# chestnut-tube-amp.net
KiCad netlist of a schematic drawn in EAGLE
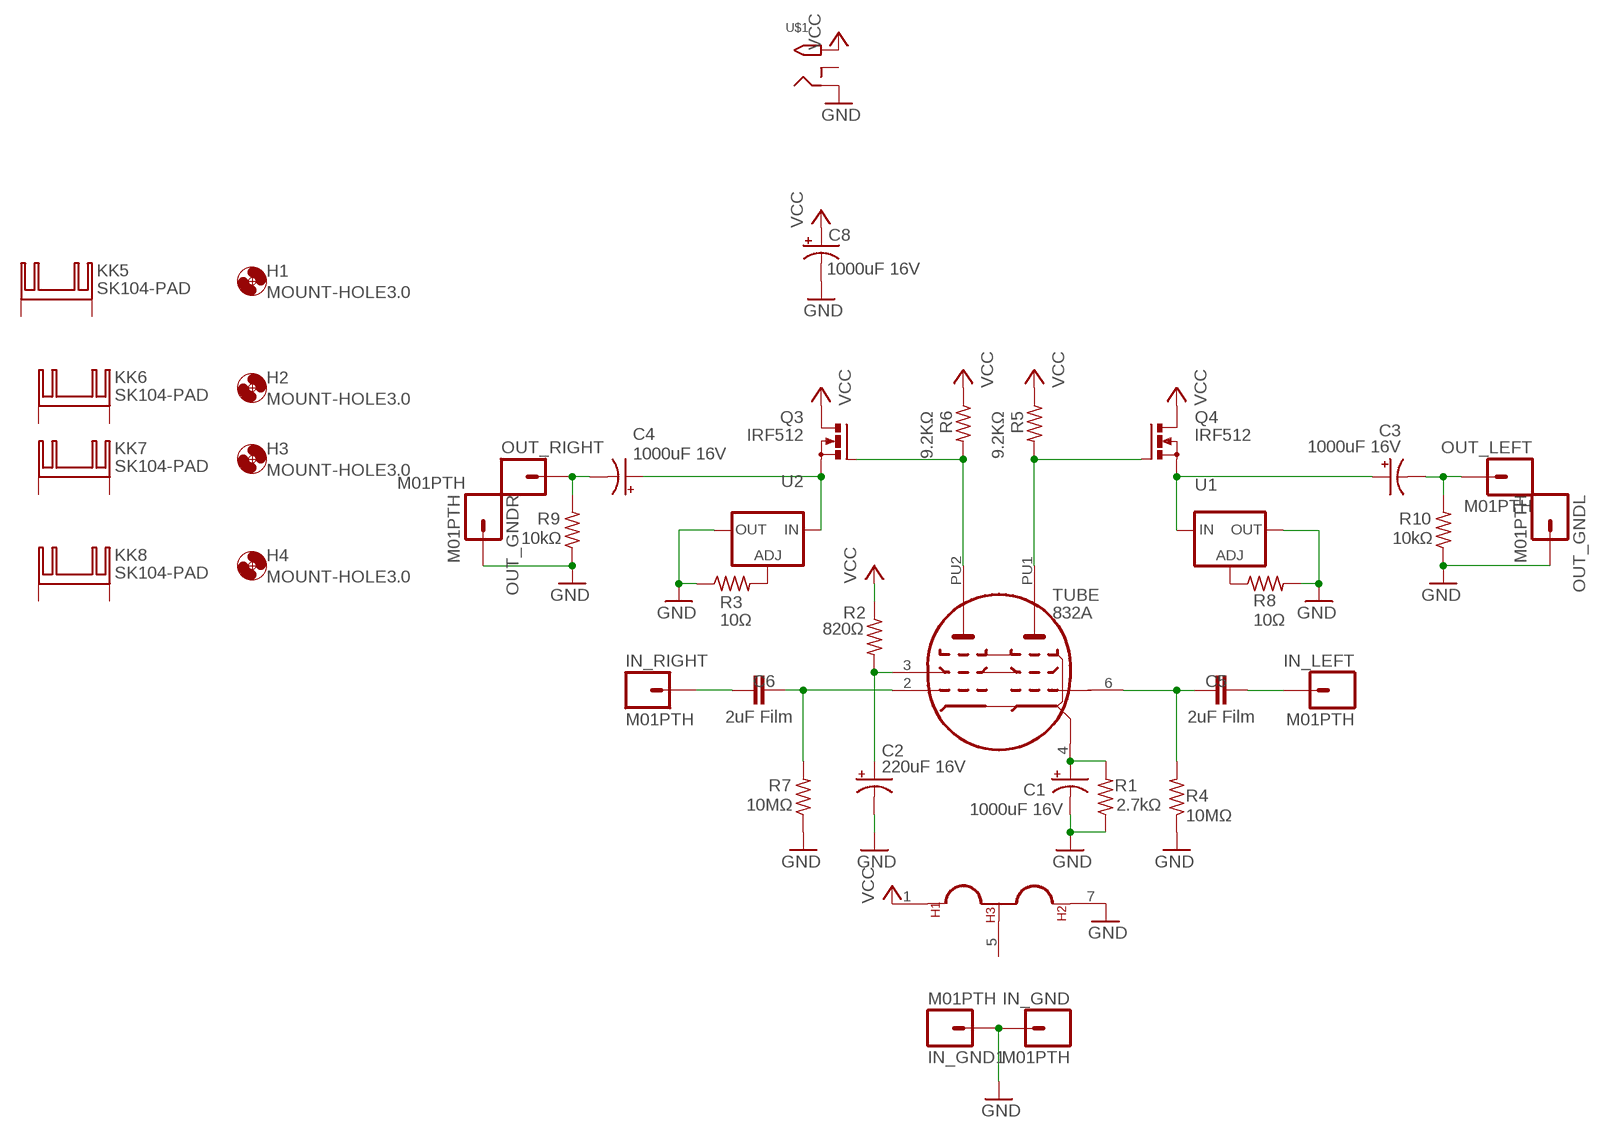
[diagram p0: schematic, sheet 1]

(export (version "E")
  (design (tool "Eeschema 10.0.6"))
  (components
    (comp (ref "C1")
      (value "1000uF 16V")
      (footprint "eagle-import:E5-10,5")
      (libsource (lib "eagle-import") (part "CPOL-USE5-10.5"))
    )
    (comp (ref "C2")
      (value "220uF 16V")
      (footprint "eagle-import:E2,5-7")
      (libsource (lib "eagle-import") (part "CPOL-USE2.5-7"))
    )
    (comp (ref "C3")
      (value "1000uF 16V")
      (footprint "eagle-import:E5-10,5")
      (libsource (lib "eagle-import") (part "CPOL-USE5-10.5"))
    )
    (comp (ref "C4")
      (value "1000uF 16V")
      (footprint "eagle-import:E5-10,5")
      (libsource (lib "eagle-import") (part "CPOL-USE5-10.5"))
    )
    (comp (ref "C5")
      (value "2uF Film")
      (footprint "eagle-import:C375-155X418")
      (libsource (lib "eagle-import") (part "C-EU375-155X418"))
    )
    (comp (ref "C6")
      (value "2uF Film")
      (footprint "eagle-import:C375-155X418")
      (libsource (lib "eagle-import") (part "C-EU375-155X418"))
    )
    (comp (ref "C8")
      (value "1000uF 16V")
      (footprint "eagle-import:E5-10,5")
      (libsource (lib "eagle-import") (part "CPOL-USE5-10.5"))
    )
    (comp (ref "H1")
      (value "MOUNT-HOLE3.0")
      (footprint "eagle-import:3,0")
      (libsource (lib "eagle-import") (part "MOUNT-HOLE3.0"))
    )
    (comp (ref "H2")
      (value "MOUNT-HOLE3.0")
      (footprint "eagle-import:3,0")
      (libsource (lib "eagle-import") (part "MOUNT-HOLE3.0"))
    )
    (comp (ref "H3")
      (value "MOUNT-HOLE3.0")
      (footprint "eagle-import:3,0")
      (libsource (lib "eagle-import") (part "MOUNT-HOLE3.0"))
    )
    (comp (ref "H4")
      (value "MOUNT-HOLE3.0")
      (footprint "eagle-import:3,0")
      (libsource (lib "eagle-import") (part "MOUNT-HOLE3.0"))
    )
    (comp (ref "IN_GND")
      (value "M01PTH")
      (footprint "eagle-import:1X01")
      (libsource (lib "eagle-import") (part "M01PTH"))
    )
    (comp (ref "IN_GND1")
      (value "M01PTH")
      (footprint "eagle-import:1X01")
      (libsource (lib "eagle-import") (part "M01PTH"))
    )
    (comp (ref "IN_LEFT")
      (value "M01PTH")
      (footprint "eagle-import:1X01")
      (libsource (lib "eagle-import") (part "M01PTH"))
    )
    (comp (ref "IN_RIGHT")
      (value "M01PTH")
      (footprint "eagle-import:1X01")
      (libsource (lib "eagle-import") (part "M01PTH"))
    )
    (comp (ref "KK5")
      (value "SK104-PAD")
      (footprint "eagle-import:SK104-PAD")
      (libsource (lib "eagle-import") (part "SK104-PAD"))
    )
    (comp (ref "KK6")
      (value "SK104-PAD")
      (footprint "eagle-import:SK104-PAD")
      (libsource (lib "eagle-import") (part "SK104-PAD"))
    )
    (comp (ref "KK7")
      (value "SK104-PAD")
      (footprint "eagle-import:SK104-PAD")
      (libsource (lib "eagle-import") (part "SK104-PAD"))
    )
    (comp (ref "KK8")
      (value "SK104-PAD")
      (footprint "eagle-import:SK104-PAD")
      (libsource (lib "eagle-import") (part "SK104-PAD"))
    )
    (comp (ref "OUT_GNDL")
      (value "M01PTH")
      (footprint "eagle-import:1X01")
      (libsource (lib "eagle-import") (part "M01PTH"))
    )
    (comp (ref "OUT_GNDR")
      (value "M01PTH")
      (footprint "eagle-import:1X01")
      (libsource (lib "eagle-import") (part "M01PTH"))
    )
    (comp (ref "OUT_LEFT")
      (value "M01PTH")
      (footprint "eagle-import:1X01")
      (libsource (lib "eagle-import") (part "M01PTH"))
    )
    (comp (ref "OUT_RIGHT")
      (value "M01PTH")
      (footprint "eagle-import:1X01")
      (libsource (lib "eagle-import") (part "M01PTH"))
    )
    (comp (ref "Q3")
      (value "IRF512")
      (footprint "eagle-import:TO220BV")
      (libsource (lib "eagle-import") (part "IRF512"))
    )
    (comp (ref "Q4")
      (value "IRF512")
      (footprint "eagle-import:TO220BV")
      (libsource (lib "eagle-import") (part "IRF512"))
    )
    (comp (ref "R1")
      (value "2.7kΩ")
      (footprint "eagle-import:0207_7")
      (libsource (lib "eagle-import") (part "R-US_0207/7"))
    )
    (comp (ref "R2")
      (value "820Ω")
      (footprint "eagle-import:0207_7")
      (libsource (lib "eagle-import") (part "R-US_0207/7"))
    )
    (comp (ref "R3")
      (value "10Ω")
      (footprint "eagle-import:0207_7")
      (libsource (lib "eagle-import") (part "R-US_0207/7"))
    )
    (comp (ref "R4")
      (value "10MΩ")
      (footprint "eagle-import:0207_7")
      (libsource (lib "eagle-import") (part "R-US_0207/7"))
    )
    (comp (ref "R5")
      (value "9.2KΩ")
      (footprint "eagle-import:0207_7")
      (libsource (lib "eagle-import") (part "R-US_0207/7"))
    )
    (comp (ref "R6")
      (value "9.2KΩ")
      (footprint "eagle-import:0207_7")
      (libsource (lib "eagle-import") (part "R-US_0207/7"))
    )
    (comp (ref "R7")
      (value "10MΩ")
      (footprint "eagle-import:0207_7")
      (libsource (lib "eagle-import") (part "R-US_0207/7"))
    )
    (comp (ref "R8")
      (value "10Ω")
      (footprint "eagle-import:0207_7")
      (libsource (lib "eagle-import") (part "R-US_0207/7"))
    )
    (comp (ref "R9")
      (value "10kΩ")
      (footprint "eagle-import:0207_7")
      (libsource (lib "eagle-import") (part "R-US_0207/7"))
    )
    (comp (ref "R10")
      (value "10kΩ")
      (footprint "eagle-import:0207_7")
      (libsource (lib "eagle-import") (part "R-US_0207/7"))
    )
    (comp (ref "TUBE")
      (value "832A")
      (footprint "eagle-import:832A")
      (libsource (lib "eagle-import") (part "832A"))
    )
    (comp (ref "U$1")
      (value "2.1MMJACKTHM")
      (footprint "eagle-import:PJ-102A")
      (libsource (lib "eagle-import") (part "2.1MMJACKTHM"))
    )
    (comp (ref "U1")
      (value "LM317TS")
      (footprint "eagle-import:317TS")
      (libsource (lib "eagle-import") (part "LM317TS"))
    )
    (comp (ref "U2")
      (value "LM317TS")
      (footprint "eagle-import:317TS")
      (libsource (lib "eagle-import") (part "LM317TS"))
    )
  )
  (nets
    (net (code "1") (name "GND") (class "Default")
      (node (ref "C1") (pin "-") (pinfunction "-_-") (pintype "passive"))
      (node (ref "C2") (pin "-") (pinfunction "-_-") (pintype "passive"))
      (node (ref "C8") (pin "-") (pinfunction "-_-") (pintype "passive"))
      (node (ref "IN_GND") (pin "1") (pinfunction "1_1") (pintype "passive"))
      (node (ref "IN_GND1") (pin "1") (pinfunction "1_1") (pintype "passive"))
      (node (ref "OUT_GNDL") (pin "1") (pinfunction "1_1") (pintype "passive"))
      (node (ref "OUT_GNDR") (pin "1") (pinfunction "1_1") (pintype "passive"))
      (node (ref "R1") (pin "1") (pinfunction "1_1") (pintype "passive"))
      (node (ref "R10") (pin "1") (pinfunction "1_1") (pintype "passive"))
      (node (ref "R3") (pin "1") (pinfunction "1_1") (pintype "passive"))
      (node (ref "R4") (pin "1") (pinfunction "1_1") (pintype "passive"))
      (node (ref "R7") (pin "1") (pinfunction "1_1") (pintype "passive"))
      (node (ref "R8") (pin "2") (pinfunction "2_2") (pintype "passive"))
      (node (ref "R9") (pin "1") (pinfunction "1_1") (pintype "passive"))
      (node (ref "TUBE") (pin "7") (pinfunction "7_7") (pintype "passive"))
      (node (ref "U$1") (pin "RING") (pinfunction "RING_RING") (pintype "bidirectional"))
      (node (ref "U1") (pin "2") (pinfunction "OUT_2") (pintype "passive"))
      (node (ref "U2") (pin "2") (pinfunction "OUT_2") (pintype "passive"))
    )
    (net (code "2") (name "Net-(C1-Pad+)") (class "Default")
      (node (ref "C1") (pin "+") (pinfunction "+_+") (pintype "passive"))
      (node (ref "R1") (pin "2") (pinfunction "2_2") (pintype "passive"))
      (node (ref "TUBE") (pin "4") (pinfunction "4_4") (pintype "passive"))
    )
    (net (code "3") (name "Net-(C2-Pad+)") (class "Default")
      (node (ref "C2") (pin "+") (pinfunction "+_+") (pintype "passive"))
      (node (ref "R2") (pin "2") (pinfunction "2_2") (pintype "passive"))
      (node (ref "TUBE") (pin "3") (pinfunction "3_3") (pintype "passive"))
    )
    (net (code "4") (name "Net-(C3-Pad-)") (class "Default")
      (node (ref "C3") (pin "-") (pinfunction "-_-") (pintype "passive"))
      (node (ref "OUT_LEFT") (pin "1") (pinfunction "1_1") (pintype "passive"))
      (node (ref "R10") (pin "2") (pinfunction "2_2") (pintype "passive"))
    )
    (net (code "5") (name "Net-(C4-Pad-)") (class "Default")
      (node (ref "C4") (pin "-") (pinfunction "-_-") (pintype "passive"))
      (node (ref "OUT_RIGHT") (pin "1") (pinfunction "1_1") (pintype "passive"))
      (node (ref "R9") (pin "2") (pinfunction "2_2") (pintype "passive"))
    )
    (net (code "6") (name "Net-(C5-Pad1)") (class "Default")
      (node (ref "C5") (pin "1") (pinfunction "1_1") (pintype "passive"))
      (node (ref "IN_LEFT") (pin "1") (pinfunction "1_1") (pintype "passive"))
    )
    (net (code "7") (name "Net-(C5-Pad2)") (class "Default")
      (node (ref "C5") (pin "2") (pinfunction "2_2") (pintype "passive"))
      (node (ref "R4") (pin "2") (pinfunction "2_2") (pintype "passive"))
      (node (ref "TUBE") (pin "6") (pinfunction "6_6") (pintype "passive"))
    )
    (net (code "8") (name "Net-(C6-Pad1)") (class "Default")
      (node (ref "C6") (pin "1") (pinfunction "1_1") (pintype "passive"))
      (node (ref "IN_RIGHT") (pin "1") (pinfunction "1_1") (pintype "passive"))
    )
    (net (code "9") (name "Net-(C6-Pad2)") (class "Default")
      (node (ref "C6") (pin "2") (pinfunction "2_2") (pintype "passive"))
      (node (ref "R7") (pin "2") (pinfunction "2_2") (pintype "passive"))
      (node (ref "TUBE") (pin "2") (pinfunction "2_2") (pintype "passive"))
    )
    (net (code "10") (name "Net-(Q3-PadG)") (class "Default")
      (node (ref "Q3") (pin "G") (pinfunction "G_G") (pintype "passive"))
      (node (ref "R6") (pin "2") (pinfunction "2_2") (pintype "passive"))
      (node (ref "TUBE") (pin "PU2") (pinfunction "PU2_PU2") (pintype "passive"))
    )
    (net (code "11") (name "Net-(Q4-PadG)") (class "Default")
      (node (ref "Q4") (pin "G") (pinfunction "G_G") (pintype "passive"))
      (node (ref "R5") (pin "2") (pinfunction "2_2") (pintype "passive"))
      (node (ref "TUBE") (pin "PU1") (pinfunction "PU1_PU1") (pintype "passive"))
    )
    (net (code "12") (name "Net-(U1-ADJ)") (class "Default")
      (node (ref "R8") (pin "1") (pinfunction "1_1") (pintype "passive"))
      (node (ref "U1") (pin "1") (pinfunction "ADJ_1") (pintype "input"))
    )
    (net (code "13") (name "Net-(U1-IN)") (class "Default")
      (node (ref "C3") (pin "+") (pinfunction "+_+") (pintype "passive"))
      (node (ref "Q4") (pin "S") (pinfunction "S_S") (pintype "passive"))
      (node (ref "U1") (pin "3") (pinfunction "IN_3") (pintype "input"))
    )
    (net (code "14") (name "Net-(U2-ADJ)") (class "Default")
      (node (ref "R3") (pin "2") (pinfunction "2_2") (pintype "passive"))
      (node (ref "U2") (pin "1") (pinfunction "ADJ_1") (pintype "input"))
    )
    (net (code "15") (name "Net-(U2-IN)") (class "Default")
      (node (ref "C4") (pin "+") (pinfunction "+_+") (pintype "passive"))
      (node (ref "Q3") (pin "S") (pinfunction "S_S") (pintype "passive"))
      (node (ref "U2") (pin "3") (pinfunction "IN_3") (pintype "input"))
    )
    (net (code "16") (name "VCC") (class "Default")
      (node (ref "C8") (pin "+") (pinfunction "+_+") (pintype "passive"))
      (node (ref "Q3") (pin "D") (pinfunction "D_D") (pintype "passive"))
      (node (ref "Q4") (pin "D") (pinfunction "D_D") (pintype "passive"))
      (node (ref "R2") (pin "1") (pinfunction "1_1") (pintype "passive"))
      (node (ref "R5") (pin "1") (pinfunction "1_1") (pintype "passive"))
      (node (ref "R6") (pin "1") (pinfunction "1_1") (pintype "passive"))
      (node (ref "TUBE") (pin "1") (pinfunction "1_1") (pintype "passive"))
      (node (ref "U$1") (pin "TIP") (pinfunction "TIP_TIP") (pintype "bidirectional"))
    )
    (net (code "17") (name "unconnected-(KK5-K-PadK1)") (class "Default")
      (node (ref "KK5") (pin "K1") (pinfunction "K_K1") (pintype "passive"))
    )
    (net (code "18") (name "unconnected-(KK5-K-PadK2)") (class "Default")
      (node (ref "KK5") (pin "K2") (pinfunction "K_K2") (pintype "passive"))
    )
    (net (code "19") (name "unconnected-(KK6-K-PadK1)") (class "Default")
      (node (ref "KK6") (pin "K1") (pinfunction "K_K1") (pintype "passive"))
    )
    (net (code "20") (name "unconnected-(KK6-K-PadK2)") (class "Default")
      (node (ref "KK6") (pin "K2") (pinfunction "K_K2") (pintype "passive"))
    )
    (net (code "21") (name "unconnected-(KK7-K-PadK1)") (class "Default")
      (node (ref "KK7") (pin "K1") (pinfunction "K_K1") (pintype "passive"))
    )
    (net (code "22") (name "unconnected-(KK7-K-PadK2)") (class "Default")
      (node (ref "KK7") (pin "K2") (pinfunction "K_K2") (pintype "passive"))
    )
    (net (code "23") (name "unconnected-(KK8-K-PadK1)") (class "Default")
      (node (ref "KK8") (pin "K1") (pinfunction "K_K1") (pintype "passive"))
    )
    (net (code "24") (name "unconnected-(KK8-K-PadK2)") (class "Default")
      (node (ref "KK8") (pin "K2") (pinfunction "K_K2") (pintype "passive"))
    )
    (net (code "25") (name "unconnected-(TUBE-Pad5)") (class "Default")
      (node (ref "TUBE") (pin "5") (pinfunction "5_5") (pintype "passive"))
    )
    (net (code "26") (name "unconnected-(U$1-PadRING_SW)") (class "Default")
      (node (ref "U$1") (pin "RING_SW") (pinfunction "RING_SW_RING_SW") (pintype "bidirectional"))
    )
  )
)
